# MeshPi.net
KiCad netlist of a schematic drawn in EAGLE
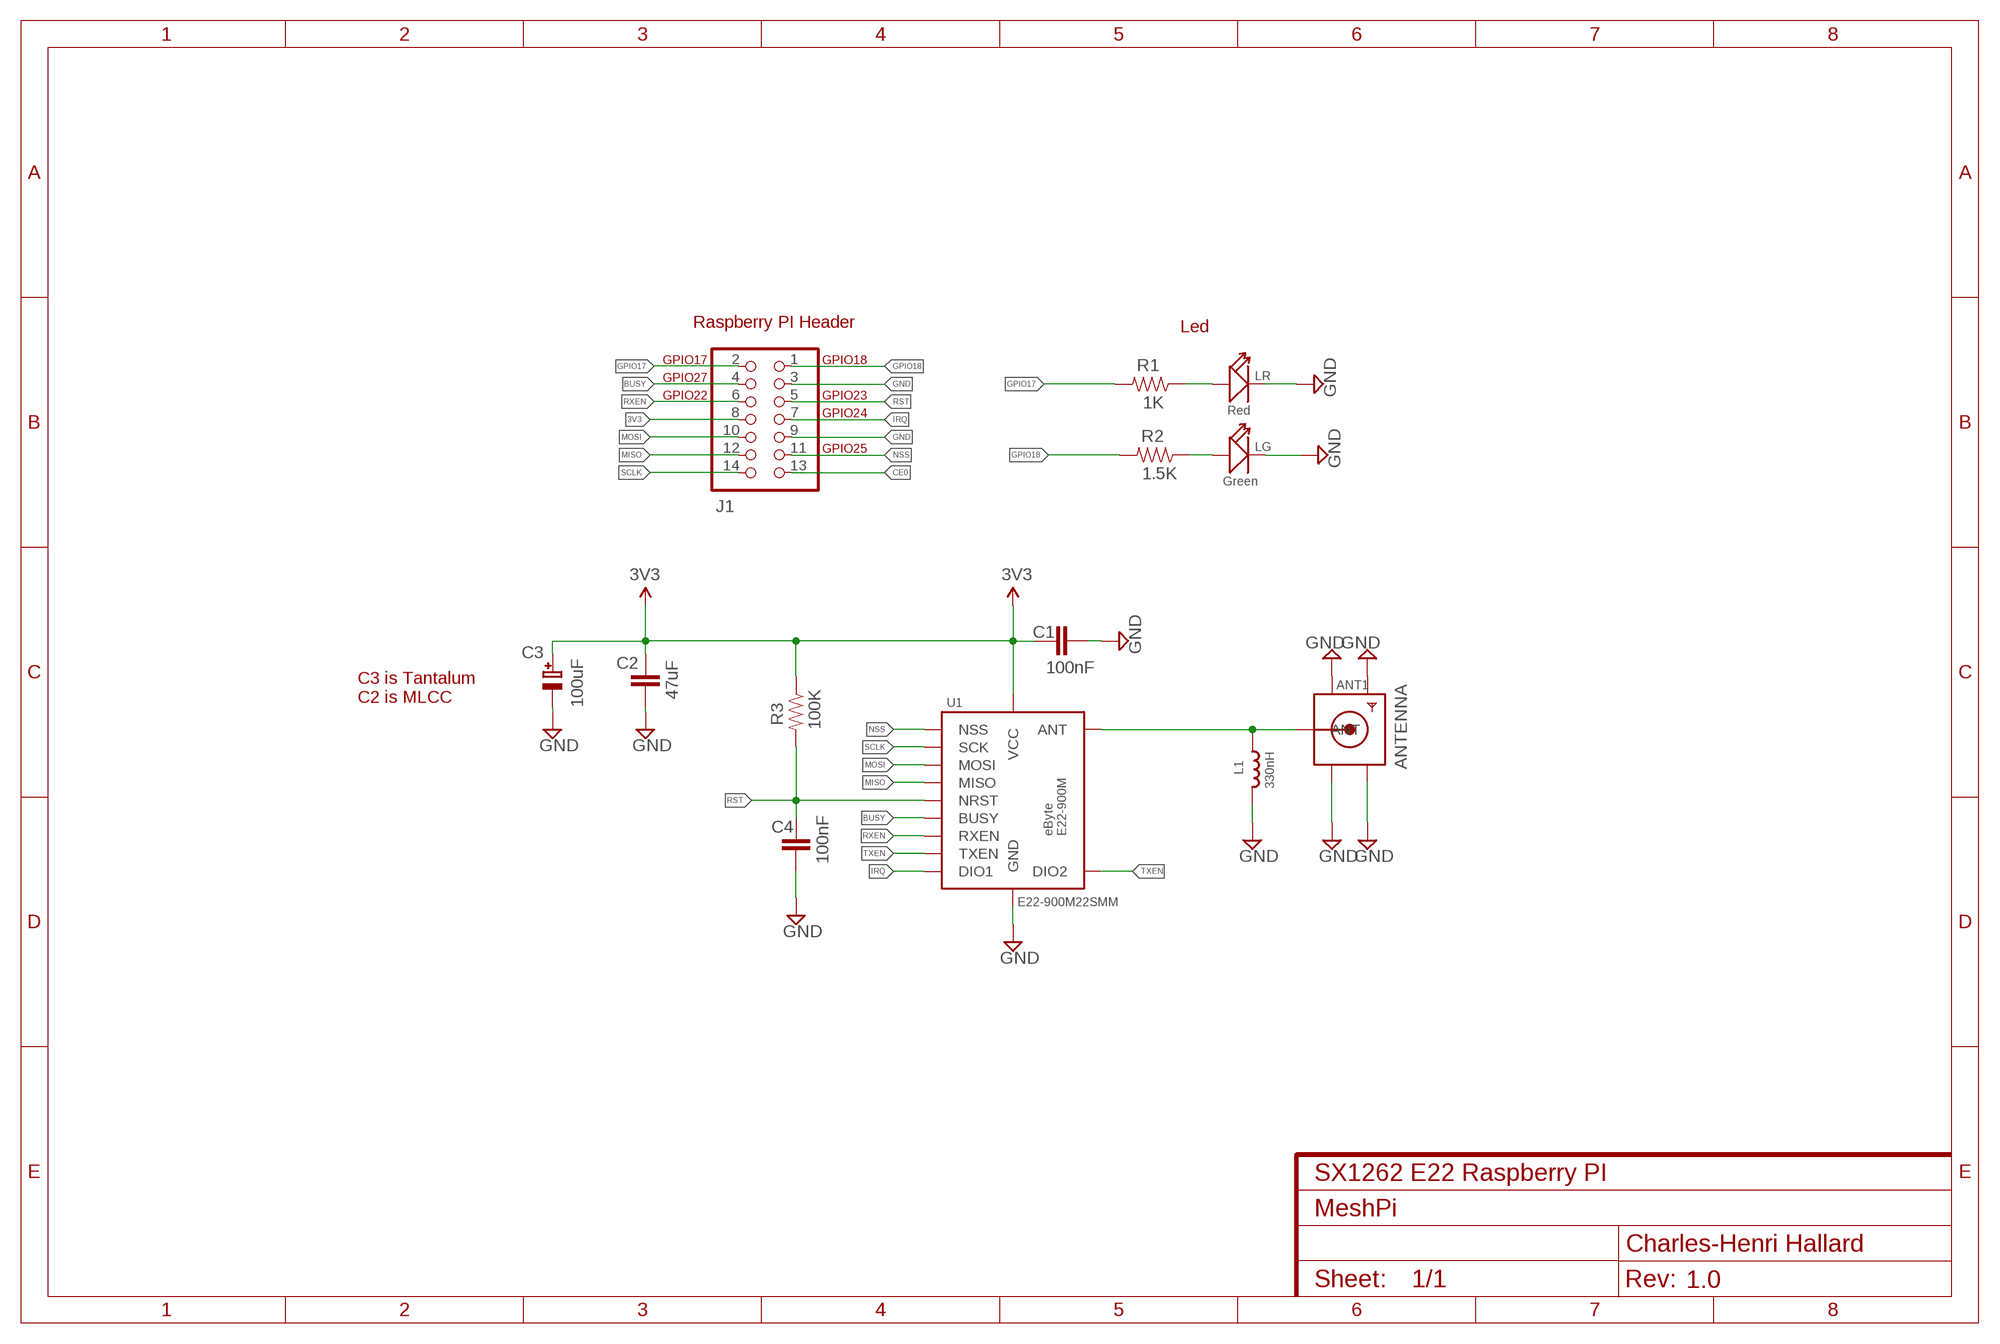
[diagram p0: schematic, sheet 1]

(export (version "E")
  (design (tool "Eeschema 10.0.6"))
  (components
    (comp (ref "ANT1")
      (value "SMACONNECTOR_EDGE_UFL")
      (footprint "eagle-import:SMA_EDGELAUNCH_UFL")
      (libsource (lib "eagle-import") (part "SMACONNECTOR_EDGE_UFL"))
    )
    (comp (ref "C1")
      (value "100nF")
      (footprint "eagle-import:0402-CAP")
      (libsource (lib "eagle-import") (part "CAP0402-CAP"))
    )
    (comp (ref "C2")
      (value "47uF")
      (footprint "eagle-import:1206")
      (libsource (lib "eagle-import") (part "CAP1206"))
    )
    (comp (ref "C3")
      (value "100uF")
      (footprint "eagle-import:EIA3528-21_B-R")
      (libsource (lib "eagle-import") (part "CAP_TANTALUMB/3528_REFLOW"))
    )
    (comp (ref "C4")
      (value "100nF")
      (footprint "eagle-import:0402-CAP")
      (libsource (lib "eagle-import") (part "CAP0402-CAP"))
    )
    (comp (ref "J1")
      (value "PINHD-2X7")
      (footprint "eagle-import:2X07")
      (libsource (lib "eagle-import") (part "PINHD-2X7"))
    )
    (comp (ref "L1")
      (value "330nH")
      (footprint "eagle-import:_0603MP")
      (libsource (lib "eagle-import") (part "INDUCTOR_0603MP"))
    )
    (comp (ref "LG")
      (value "Green")
      (footprint "eagle-import:LED-0402")
      (fields (field (name "MPN") "BL-HB337A-AV-TRB"))
      (libsource (lib "eagle-import") (part "SMD-LED-CLEAR-BLUE(0402)"))
    )
    (comp (ref "LR")
      (value "Red")
      (footprint "eagle-import:LED-0402")
      (fields (field (name "MPN") "BL-HB337A-AV-TRB"))
      (libsource (lib "eagle-import") (part "SMD-LED-CLEAR-BLUE(0402)"))
    )
    (comp (ref "R1")
      (value "1K")
      (footprint "eagle-import:0402-RES")
      (libsource (lib "eagle-import") (part "RESISTOR0402-RES"))
    )
    (comp (ref "R2")
      (value "1.5K")
      (footprint "eagle-import:0402-RES")
      (libsource (lib "eagle-import") (part "RESISTOR0402-RES"))
    )
    (comp (ref "R3")
      (value "100K")
      (footprint "eagle-import:0402-RES")
      (libsource (lib "eagle-import") (part "RESISTOR0402-RES"))
    )
    (comp (ref "U1")
      (value "E22-900M22SMM")
      (footprint "eagle-import:E22-900MM2S")
      (libsource (lib "eagle-import") (part "E22-900M22SMM"))
    )
  )
  (nets
    (net (code "1") (name "/ANTENNA") (class "Default")
      (node (ref "ANT1") (pin "P") (pinfunction "ANT_P") (pintype "bidirectional"))
      (node (ref "L1") (pin "1") (pinfunction "1_1") (pintype "passive"))
      (node (ref "U1") (pin "P$6") (pinfunction "ANT_P$6") (pintype "output"))
    )
    (net (code "2") (name "3V3") (class "Default")
      (node (ref "C1") (pin "2") (pinfunction "2_2") (pintype "passive"))
      (node (ref "C2") (pin "2") (pinfunction "2_2") (pintype "passive"))
      (node (ref "C3") (pin "+") (pinfunction "+_+") (pintype "passive"))
      (node (ref "J1") (pin "8") (pinfunction "8_8") (pintype "passive"))
      (node (ref "R3") (pin "1") (pinfunction "1_1") (pintype "passive"))
      (node (ref "U1") (pin "P$1") (pinfunction "VCC_P$1") (pintype "power_in"))
    )
    (net (code "3") (name "BUSY") (class "Default")
      (node (ref "J1") (pin "4") (pinfunction "4_4") (pintype "passive"))
      (node (ref "U1") (pin "P$11") (pinfunction "BUSY_P$11") (pintype "bidirectional"))
    )
    (net (code "4") (name "CE0") (class "Default")
      (node (ref "J1") (pin "13") (pinfunction "13_13") (pintype "passive"))
    )
    (net (code "5") (name "GND") (class "Default")
      (node (ref "ANT1") (pin "GND@1") (pinfunction "GND1_GND@1") (pintype "power_in"))
      (node (ref "ANT1") (pin "GND@2") (pinfunction "GND2_GND@2") (pintype "power_in"))
      (node (ref "ANT1") (pin "GND@3") (pinfunction "GND3_GND@3") (pintype "power_in"))
      (node (ref "ANT1") (pin "GND@4") (pinfunction "GND4_GND@4") (pintype "power_in"))
      (node (ref "C1") (pin "1") (pinfunction "1_1") (pintype "passive"))
      (node (ref "C2") (pin "1") (pinfunction "1_1") (pintype "passive"))
      (node (ref "C3") (pin "-") (pinfunction "-_-") (pintype "passive"))
      (node (ref "C4") (pin "1") (pinfunction "1_1") (pintype "passive"))
      (node (ref "J1") (pin "3") (pinfunction "3_3") (pintype "passive"))
      (node (ref "J1") (pin "9") (pinfunction "9_9") (pintype "passive"))
      (node (ref "L1") (pin "2") (pinfunction "2_2") (pintype "passive"))
      (node (ref "LG") (pin "-") (pinfunction "-_-") (pintype "passive"))
      (node (ref "LR") (pin "-") (pinfunction "-_-") (pintype "passive"))
      (node (ref "U1") (pin "P$16") (pinfunction "GND_P$16") (pintype "power_in"))
      (node (ref "U1") (pin "P$2") (pinfunction "GND_P$2") (pintype "power_in"))
      (node (ref "U1") (pin "P$7") (pinfunction "GND_P$7") (pintype "power_in"))
    )
    (net (code "6") (name "GPIO17") (class "Default")
      (node (ref "J1") (pin "2") (pinfunction "2_2") (pintype "passive"))
      (node (ref "R1") (pin "2") (pinfunction "2_2") (pintype "passive"))
    )
    (net (code "7") (name "GPIO18") (class "Default")
      (node (ref "J1") (pin "1") (pinfunction "1_1") (pintype "passive"))
      (node (ref "R2") (pin "2") (pinfunction "2_2") (pintype "passive"))
    )
    (net (code "8") (name "IRQ") (class "Default")
      (node (ref "J1") (pin "7") (pinfunction "7_7") (pintype "passive"))
      (node (ref "U1") (pin "P$20") (pinfunction "DIO1_P$20") (pintype "bidirectional"))
    )
    (net (code "9") (name "MISO") (class "Default")
      (node (ref "J1") (pin "12") (pinfunction "12_12") (pintype "passive"))
      (node (ref "U1") (pin "P$12") (pinfunction "MISO_P$12") (pintype "bidirectional"))
    )
    (net (code "10") (name "MOSI") (class "Default")
      (node (ref "J1") (pin "10") (pinfunction "10_10") (pintype "passive"))
      (node (ref "U1") (pin "P$13") (pinfunction "MOSI_P$13") (pintype "bidirectional"))
    )
    (net (code "11") (name "NSS") (class "Default")
      (node (ref "J1") (pin "11") (pinfunction "11_11") (pintype "passive"))
      (node (ref "U1") (pin "P$14") (pinfunction "NSS_P$14") (pintype "input"))
    )
    (net (code "12") (name "Net-(LG-Pad+)") (class "Default")
      (node (ref "LG") (pin "+") (pinfunction "+_+") (pintype "passive"))
      (node (ref "R2") (pin "1") (pinfunction "1_1") (pintype "passive"))
    )
    (net (code "13") (name "Net-(LR-Pad+)") (class "Default")
      (node (ref "LR") (pin "+") (pinfunction "+_+") (pintype "passive"))
      (node (ref "R1") (pin "1") (pinfunction "1_1") (pintype "passive"))
    )
    (net (code "14") (name "RST") (class "Default")
      (node (ref "C4") (pin "2") (pinfunction "2_2") (pintype "passive"))
      (node (ref "J1") (pin "5") (pinfunction "5_5") (pintype "passive"))
      (node (ref "R3") (pin "2") (pinfunction "2_2") (pintype "passive"))
      (node (ref "U1") (pin "P$3") (pinfunction "NRST_P$3") (pintype "bidirectional"))
    )
    (net (code "15") (name "RXEN") (class "Default")
      (node (ref "J1") (pin "6") (pinfunction "6_6") (pintype "passive"))
      (node (ref "U1") (pin "P$10") (pinfunction "RXEN_P$10") (pintype "input"))
    )
    (net (code "16") (name "SCLK") (class "Default")
      (node (ref "J1") (pin "14") (pinfunction "14_14") (pintype "passive"))
      (node (ref "U1") (pin "P$15") (pinfunction "SCK_P$15") (pintype "input"))
    )
    (net (code "17") (name "TXEN") (class "Default")
      (node (ref "U1") (pin "P$19") (pinfunction "DIO2_P$19") (pintype "bidirectional"))
      (node (ref "U1") (pin "P$9") (pinfunction "TXEN_P$9") (pintype "bidirectional"))
    )
  )
)
